# main_esp.net
KiCad netlist of a schematic drawn in Altium Designer
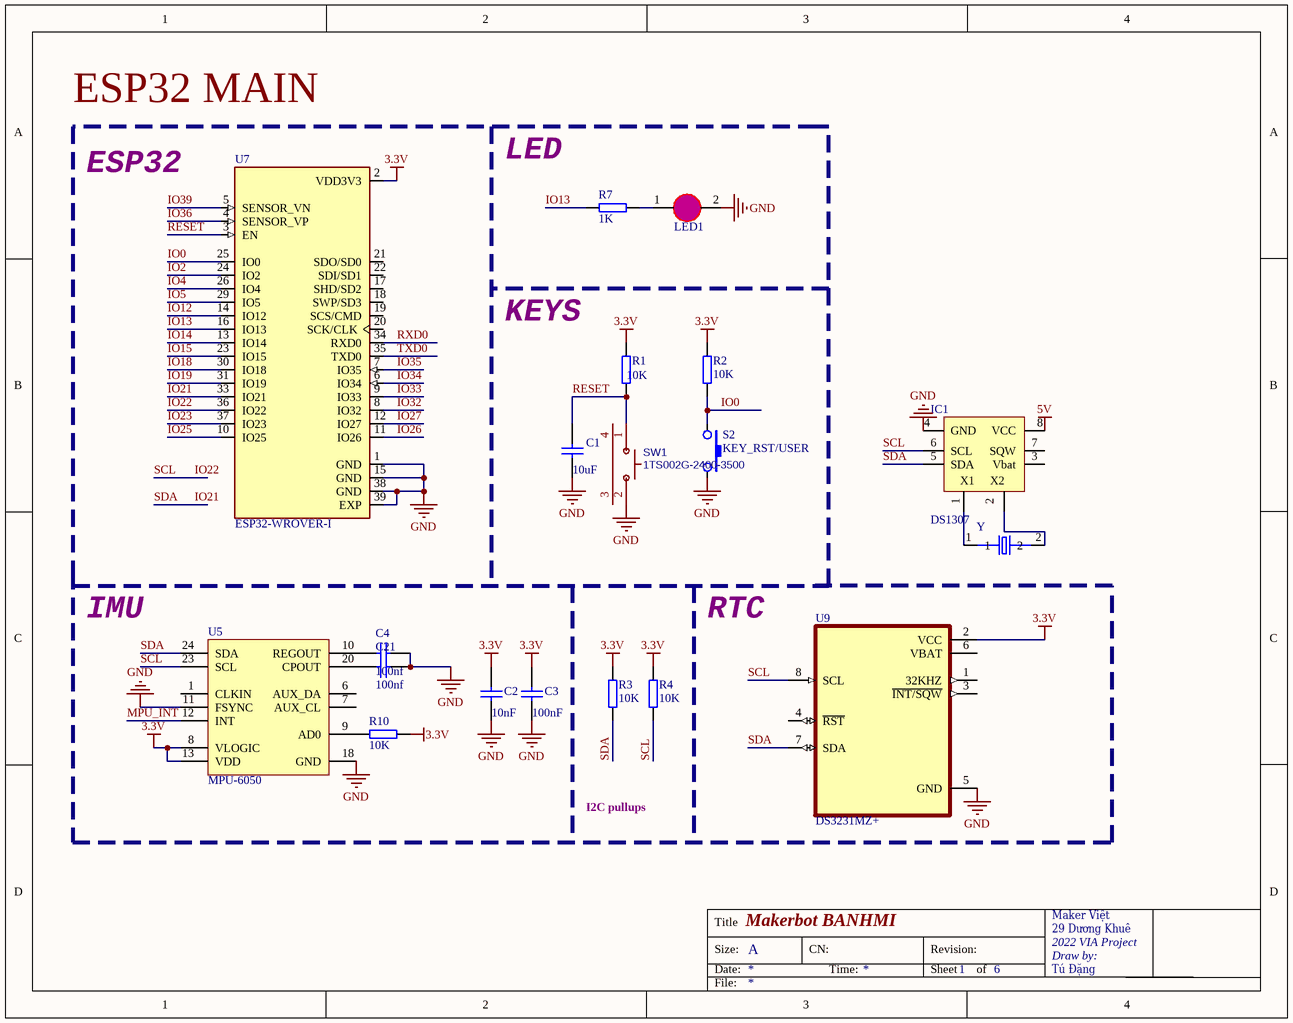
[diagram p0: main_esp.SchDoc]

(export (version "E")
  (design (tool "Eeschema 10.0.6"))
  (components
    (comp (ref "C1")
      (value "10uF")
      (footprint "SMT0603")
      (description "CAP SM 0603 X5R 10uF 10%")
      (fields (field (name "TOLERANCE") "±10%") (field (name "Comment") "Cap Semi"))
      (libsource (lib "electronpowered") (part "CAP-SM-0603-X5R-10uF"))
    )
    (comp (ref "C2")
      (value "10nF")
      (footprint "SMT0603")
      (description "CAP SM 0603 X5R 10uF 10%")
      (fields (field (name "TOLERANCE") "±10%") (field (name "Comment") "Cap Semi"))
      (libsource (lib "electronpowered") (part "CAP-SM-0603-X5R-10uF"))
    )
    (comp (ref "C3")
      (value "100nF")
      (footprint "SMT0603")
      (description "CAP SM 0603 X7R 100nF 10%")
      (fields (field (name "TOLERANCE") "±10%") (field (name "Comment") "Cap Semi"))
      (libsource (lib "electronpowered") (part "CAP-SM-0603-X7R-100nF"))
    )
    (comp (ref "C4")
      (value "100nf")
      (footprint "SMT0603")
      (description "CAP SM 0603 X5R 10uF 10%")
      (fields (field (name "TOLERANCE") "±10%") (field (name "Comment") "Cap Semi"))
      (libsource (lib "electronpowered") (part "CAP-SM-0603-X5R-10uF"))
    )
    (comp (ref "C21")
      (value "100nf")
      (footprint "SMT0603")
      (description "CAP SM 0603 X5R 10uF 10%")
      (fields (field (name "TOLERANCE") "±10%") (field (name "Comment") "Cap Semi"))
      (libsource (lib "electronpowered") (part "CAP-SM-0603-X5R-10uF"))
    )
    (comp (ref "IC1")
      (value "DS1307")
      (footprint "SOIC-8")
      (description "Real Timer Serial")
      (libsource (lib "My Library") (part "DS1307"))
    )
    (comp (ref "LED1")
      (value "LED3")
      (footprint "LED0805")
      (description "LED SMD 0805")
      (libsource (lib "My Library") (part "LED0805"))
    )
    (comp (ref "R1")
      (value "10K")
      (footprint "SMT0603")
      (description "RES SM 0603 10K")
      (fields (field (name "Comment") "Resistor"))
      (libsource (lib "electronpowered") (part "RES-SM-0603-10K"))
    )
    (comp (ref "R2")
      (value "10K")
      (footprint "SMT0603")
      (description "RES SM 0603 10K")
      (fields (field (name "Comment") "Resistor"))
      (libsource (lib "electronpowered") (part "RES-SM-0603-10K"))
    )
    (comp (ref "R3")
      (value "10K")
      (footprint "SMT0603")
      (description "RES SM 0603 10K")
      (fields (field (name "Comment") "Resistor"))
      (libsource (lib "electronpowered") (part "RES-SM-0603-10K"))
    )
    (comp (ref "R4")
      (value "10K")
      (footprint "SMT0603")
      (description "RES SM 0603 10K")
      (fields (field (name "Comment") "Resistor"))
      (libsource (lib "electronpowered") (part "RES-SM-0603-10K"))
    )
    (comp (ref "R7")
      (value "1K")
      (footprint "SMT0603")
      (description "RES SM 0603 1K")
      (fields (field (name "Comment") "Resistor"))
      (libsource (lib "electronpowered") (part "RES-SM-0603-1K"))
    )
    (comp (ref "R10")
      (value "10K")
      (footprint "SMT0603")
      (description "RES SM 0603 10K")
      (fields (field (name "Comment") "Resistor"))
      (libsource (lib "electronpowered") (part "RES-SM-0603-10K"))
    )
    (comp (ref "S2")
      (value "KEY_RST/USER")
      (footprint "SMT_SW_PTS_820")
      (description "SMT Tactile ‎Switch PTS 820 Series")
      (libsource (lib "NODEMCU_DEVKIT_V1.0") (part "SMT_SW_PTS_820"))
    )
    (comp (ref "SW1")
      (value "1TS002G-2400-3500")
      (footprint "KEY-SMD_1TS002G")
      (fields (field (name "BOM_SUPPLIER PART") "C319378") (field (name "CONTRIBUTOR") "LCSC"))
      (libsource (lib "SW") (part "1TS002G-2400-3500"))
    )
    (comp (ref "U5") (value "MPU-6050") (footprint "MPU-6050") (libsource (lib "MPU-6050") (part "MPU-6050")))
    (comp (ref "U7")
      (value "ESP32-WROVER-I")
      (footprint "SnapEDApcb:XCVR_ESP32-WROVER-I")
      (fields (field (name "MF") "Espressif Systems"))
      (libsource (lib "SnapEDAsch") (part "ESP32-WROVER-I"))
    )
    (comp (ref "U9")
      (value "DS3231MZ+")
      (footprint "SOIC127P600X175-8N")
      (description "Real Time Clock _RTC_ IC Clock/Calendar IÂ²C, 2-Wire Serial 8-SOIC _0.154, 3.90mm Width_")
      (fields (field (name "MP") "DS3231MZ") (field (name "MF") "Maxim Integrated"))
      (libsource (lib "DS3231MZ_") (part "DS3231MZ+"))
    )
    (comp (ref "Y")
      (value "ABS07AIG-32.768KHZ-7-1-T")
      (footprint "XTAL320X150X90")
      (description "32.768kHz Â±10ppm Crystal 7pF 80 kOhms 2-SMD, No Lead")
      (fields (field (name "DIGI-KEY_PART_NUMBER") "535-13354-1-ND") (field (name "MF") "Abracon"))
      (libsource (lib "ABS07AIG-32.768KHZ-7-1-T") (part "ABS07AIG-32.768KHZ-7-1-T"))
    )
  )
  (nets
    (net (code "1") (name "/IO0") (class "Default")
      (node (ref "R2") (pin "1") (pinfunction "1_1") (pintype "passive"))
      (node (ref "S2") (pin "1") (pinfunction "1_1") (pintype "passive"))
      (node (ref "U7") (pin "25") (pinfunction "IO0_25") (pintype "bidirectional"))
    )
    (net (code "2") (name "/IO2") (class "Default")
      (node (ref "U7") (pin "24") (pinfunction "IO2_24") (pintype "bidirectional"))
    )
    (net (code "3") (name "/IO4") (class "Default")
      (node (ref "U7") (pin "26") (pinfunction "IO4_26") (pintype "bidirectional"))
    )
    (net (code "4") (name "/IO5") (class "Default")
      (node (ref "U7") (pin "29") (pinfunction "IO5_29") (pintype "bidirectional"))
    )
    (net (code "5") (name "/IO12") (class "Default")
      (node (ref "U7") (pin "14") (pinfunction "IO12_14") (pintype "bidirectional"))
    )
    (net (code "6") (name "/IO13") (class "Default")
      (node (ref "R7") (pin "1") (pinfunction "1_1") (pintype "passive"))
      (node (ref "U7") (pin "16") (pinfunction "IO13_16") (pintype "bidirectional"))
    )
    (net (code "7") (name "/IO14") (class "Default")
      (node (ref "U7") (pin "13") (pinfunction "IO14_13") (pintype "bidirectional"))
    )
    (net (code "8") (name "/IO15") (class "Default")
      (node (ref "U7") (pin "23") (pinfunction "IO15_23") (pintype "bidirectional"))
    )
    (net (code "9") (name "/IO18") (class "Default")
      (node (ref "U7") (pin "30") (pinfunction "IO18_30") (pintype "bidirectional"))
    )
    (net (code "10") (name "/IO19") (class "Default")
      (node (ref "U7") (pin "31") (pinfunction "IO19_31") (pintype "bidirectional"))
    )
    (net (code "11") (name "/IO21") (class "Default")
      (node (ref "IC1") (pin "5") (pinfunction "SDA_5") (pintype "passive"))
      (node (ref "R3") (pin "1") (pinfunction "1_1") (pintype "passive"))
      (node (ref "U5") (pin "24") (pinfunction "SDA_24") (pintype "passive"))
      (node (ref "U7") (pin "33") (pinfunction "IO21_33") (pintype "bidirectional"))
      (node (ref "U9") (pin "7") (pinfunction "SDA_7") (pintype "bidirectional"))
    )
    (net (code "12") (name "/IO22") (class "Default")
      (node (ref "IC1") (pin "6") (pinfunction "SCL_6") (pintype "passive"))
      (node (ref "R4") (pin "1") (pinfunction "1_1") (pintype "passive"))
      (node (ref "U5") (pin "23") (pinfunction "SCL_23") (pintype "passive"))
      (node (ref "U7") (pin "36") (pinfunction "IO22_36") (pintype "bidirectional"))
      (node (ref "U9") (pin "8") (pinfunction "SCL_8") (pintype "input"))
    )
    (net (code "13") (name "/IO23") (class "Default")
      (node (ref "U7") (pin "37") (pinfunction "IO23_37") (pintype "bidirectional"))
    )
    (net (code "14") (name "/IO25") (class "Default")
      (node (ref "U7") (pin "10") (pinfunction "IO25_10") (pintype "bidirectional"))
    )
    (net (code "15") (name "/IO26") (class "Default")
      (node (ref "U7") (pin "11") (pinfunction "IO26_11") (pintype "bidirectional"))
    )
    (net (code "16") (name "/IO27") (class "Default")
      (node (ref "U7") (pin "12") (pinfunction "IO27_12") (pintype "bidirectional"))
    )
    (net (code "17") (name "/IO32") (class "Default")
      (node (ref "U7") (pin "8") (pinfunction "IO32_8") (pintype "bidirectional"))
    )
    (net (code "18") (name "/IO33") (class "Default")
      (node (ref "U7") (pin "9") (pinfunction "IO33_9") (pintype "bidirectional"))
    )
    (net (code "19") (name "/IO34") (class "Default")
      (node (ref "U7") (pin "6") (pinfunction "IO34_6") (pintype "input"))
    )
    (net (code "20") (name "/IO35") (class "Default")
      (node (ref "U7") (pin "7") (pinfunction "IO35_7") (pintype "input"))
    )
    (net (code "21") (name "/IO36") (class "Default")
      (node (ref "U7") (pin "4") (pinfunction "SENSOR_VP_4") (pintype "input"))
    )
    (net (code "22") (name "/IO39") (class "Default")
      (node (ref "U7") (pin "5") (pinfunction "SENSOR_VN_5") (pintype "input"))
    )
    (net (code "23") (name "/MPU_INT") (class "Default")
      (node (ref "U5") (pin "12") (pinfunction "INT_12") (pintype "passive"))
    )
    (net (code "24") (name "/RESET") (class "Default")
      (node (ref "C1") (pin "2") (pinfunction "2_2") (pintype "passive"))
      (node (ref "R1") (pin "1") (pinfunction "1_1") (pintype "passive"))
      (node (ref "SW1") (pin "1") (pinfunction "1_1") (pintype "passive"))
      (node (ref "U7") (pin "3") (pinfunction "EN_3") (pintype "input"))
    )
    (net (code "25") (name "/RXD0") (class "Default")
      (node (ref "U7") (pin "34") (pinfunction "RXD0_34") (pintype "bidirectional"))
    )
    (net (code "26") (name "/TXD0") (class "Default")
      (node (ref "U7") (pin "35") (pinfunction "TXD0_35") (pintype "bidirectional"))
    )
    (net (code "27") (name "3.3V") (class "Default")
      (node (ref "C2") (pin "2") (pinfunction "2_2") (pintype "passive"))
      (node (ref "C3") (pin "2") (pinfunction "2_2") (pintype "passive"))
      (node (ref "R1") (pin "2") (pinfunction "2_2") (pintype "passive"))
      (node (ref "R10") (pin "1") (pinfunction "1_1") (pintype "passive"))
      (node (ref "R2") (pin "2") (pinfunction "2_2") (pintype "passive"))
      (node (ref "R3") (pin "2") (pinfunction "2_2") (pintype "passive"))
      (node (ref "R4") (pin "2") (pinfunction "2_2") (pintype "passive"))
      (node (ref "U5") (pin "13") (pinfunction "VDD_13") (pintype "passive"))
      (node (ref "U5") (pin "8") (pinfunction "VLOGIC_8") (pintype "passive"))
      (node (ref "U7") (pin "2") (pinfunction "VDD3V3_2") (pintype "power_in"))
      (node (ref "U9") (pin "2") (pinfunction "VCC_2") (pintype "power_in"))
    )
    (net (code "28") (name "5V") (class "Default")
      (node (ref "IC1") (pin "8") (pinfunction "VCC_8") (pintype "passive"))
    )
    (net (code "29") (name "GND") (class "Default")
      (node (ref "C1") (pin "1") (pinfunction "1_1") (pintype "passive"))
      (node (ref "C2") (pin "1") (pinfunction "1_1") (pintype "passive"))
      (node (ref "C21") (pin "1") (pinfunction "1_1") (pintype "passive"))
      (node (ref "C3") (pin "1") (pinfunction "1_1") (pintype "passive"))
      (node (ref "C4") (pin "1") (pinfunction "1_1") (pintype "passive"))
      (node (ref "IC1") (pin "4") (pinfunction "GND_4") (pintype "passive"))
      (node (ref "LED1") (pin "2") (pinfunction "K_2") (pintype "passive"))
      (node (ref "S2") (pin "2") (pinfunction "2_2") (pintype "passive"))
      (node (ref "SW1") (pin "2") (pinfunction "2_2") (pintype "passive"))
      (node (ref "U5") (pin "11") (pinfunction "FSYNC_11") (pintype "passive"))
      (node (ref "U5") (pin "18") (pinfunction "GND_18") (pintype "passive"))
      (node (ref "U7") (pin "1") (pinfunction "GND_1") (pintype "power_in"))
      (node (ref "U7") (pin "15") (pinfunction "GND_15") (pintype "power_in"))
      (node (ref "U7") (pin "38") (pinfunction "GND_38") (pintype "power_in"))
      (node (ref "U7") (pin "39") (pinfunction "EXP_39") (pintype "power_in"))
      (node (ref "U9") (pin "5") (pinfunction "GND_5") (pintype "power_in"))
    )
    (net (code "30") (name "Net-(IC1-X1)") (class "Default")
      (node (ref "IC1") (pin "1") (pinfunction "X1_1") (pintype "passive"))
      (node (ref "Y") (pin "1") (pinfunction "1_1") (pintype "passive"))
    )
    (net (code "31") (name "Net-(IC1-X2)") (class "Default")
      (node (ref "IC1") (pin "2") (pinfunction "X2_2") (pintype "passive"))
      (node (ref "Y") (pin "2") (pinfunction "2_2") (pintype "passive"))
    )
    (net (code "32") (name "Net-(LED1-A)") (class "Default")
      (node (ref "LED1") (pin "1") (pinfunction "A_1") (pintype "passive"))
      (node (ref "R7") (pin "2") (pinfunction "2_2") (pintype "passive"))
    )
    (net (code "33") (name "Net-(U5-AD0)") (class "Default")
      (node (ref "R10") (pin "2") (pinfunction "2_2") (pintype "passive"))
      (node (ref "U5") (pin "9") (pinfunction "AD0_9") (pintype "passive"))
    )
    (net (code "34") (name "Net-(U5-CPOUT)") (class "Default")
      (node (ref "C21") (pin "2") (pinfunction "2_2") (pintype "passive"))
      (node (ref "U5") (pin "20") (pinfunction "CPOUT_20") (pintype "passive"))
    )
    (net (code "35") (name "Net-(U5-REGOUT)") (class "Default")
      (node (ref "C4") (pin "2") (pinfunction "2_2") (pintype "passive"))
      (node (ref "U5") (pin "10") (pinfunction "REGOUT_10") (pintype "passive"))
    )
    (net (code "36") (name "VCC") (class "Default")
      (node (ref "IC1") (pin "8") (pinfunction "VCC_8") (pintype "passive"))
    )
    (net (code "37") (name "unconnected-(IC1-GND-Pad4)") (class "Default")
      (node (ref "IC1") (pin "4") (pinfunction "GND_4") (pintype "passive"))
    )
    (net (code "38") (name "unconnected-(IC1-SQW-Pad7)") (class "Default")
      (node (ref "IC1") (pin "7") (pinfunction "SQW_7") (pintype "passive"))
    )
    (net (code "39") (name "unconnected-(IC1-Vbat-Pad3)") (class "Default")
      (node (ref "IC1") (pin "3") (pinfunction "Vbat_3") (pintype "passive"))
    )
    (net (code "40") (name "unconnected-(SW1-Pad3)") (class "Default")
      (node (ref "SW1") (pin "3") (pinfunction "3_3") (pintype "passive"))
    )
    (net (code "41") (name "unconnected-(SW1-Pad4)") (class "Default")
      (node (ref "SW1") (pin "4") (pinfunction "4_4") (pintype "passive"))
    )
    (net (code "42") (name "unconnected-(U5-AUX_CL-Pad7)") (class "Default")
      (node (ref "U5") (pin "7") (pinfunction "AUX_CL_7") (pintype "passive"))
    )
    (net (code "43") (name "unconnected-(U5-AUX_DA-Pad6)") (class "Default")
      (node (ref "U5") (pin "6") (pinfunction "AUX_DA_6") (pintype "passive"))
    )
    (net (code "44") (name "unconnected-(U5-CLKIN-Pad1)") (class "Default")
      (node (ref "U5") (pin "1") (pinfunction "CLKIN_1") (pintype "passive"))
    )
    (net (code "45") (name "unconnected-(U7-SCK{slash}CLK-Pad20)") (class "Default")
      (node (ref "U7") (pin "20") (pinfunction "SCK/CLK_20") (pintype "bidirectional"))
    )
    (net (code "46") (name "unconnected-(U7-SCS{slash}CMD-Pad19)") (class "Default")
      (node (ref "U7") (pin "19") (pinfunction "SCS/CMD_19") (pintype "bidirectional"))
    )
    (net (code "47") (name "unconnected-(U7-SDI{slash}SD1-Pad22)") (class "Default")
      (node (ref "U7") (pin "22") (pinfunction "SDI/SD1_22") (pintype "bidirectional"))
    )
    (net (code "48") (name "unconnected-(U7-SDO{slash}SD0-Pad21)") (class "Default")
      (node (ref "U7") (pin "21") (pinfunction "SDO/SD0_21") (pintype "bidirectional"))
    )
    (net (code "49") (name "unconnected-(U7-SHD{slash}SD2-Pad17)") (class "Default")
      (node (ref "U7") (pin "17") (pinfunction "SHD/SD2_17") (pintype "bidirectional"))
    )
    (net (code "50") (name "unconnected-(U7-SWP{slash}SD3-Pad18)") (class "Default")
      (node (ref "U7") (pin "18") (pinfunction "SWP/SD3_18") (pintype "bidirectional"))
    )
    (net (code "51") (name "unconnected-(U9-32KHZ-Pad1)") (class "Default")
      (node (ref "U9") (pin "1") (pinfunction "32KHZ_1") (pintype "output"))
    )
    (net (code "52") (name "unconnected-(U9-VBAT-Pad6)") (class "Default")
      (node (ref "U9") (pin "6") (pinfunction "VBAT_6") (pintype "power_in"))
    )
    (net (code "53") (name "unconnected-(U9-~{INT{slash}SQW}-Pad3)") (class "Default")
      (node (ref "U9") (pin "3") (pinfunction "~{INT/SQW}_3") (pintype "output"))
    )
    (net (code "54") (name "unconnected-(U9-~{RST}-Pad4)") (class "Default")
      (node (ref "U9") (pin "4") (pinfunction "~{RST}_4") (pintype "bidirectional"))
    )
  )
)
